# MJ818_clone_-_all_driver_-_prod.net
KiCad netlist of a schematic drawn in EAGLE
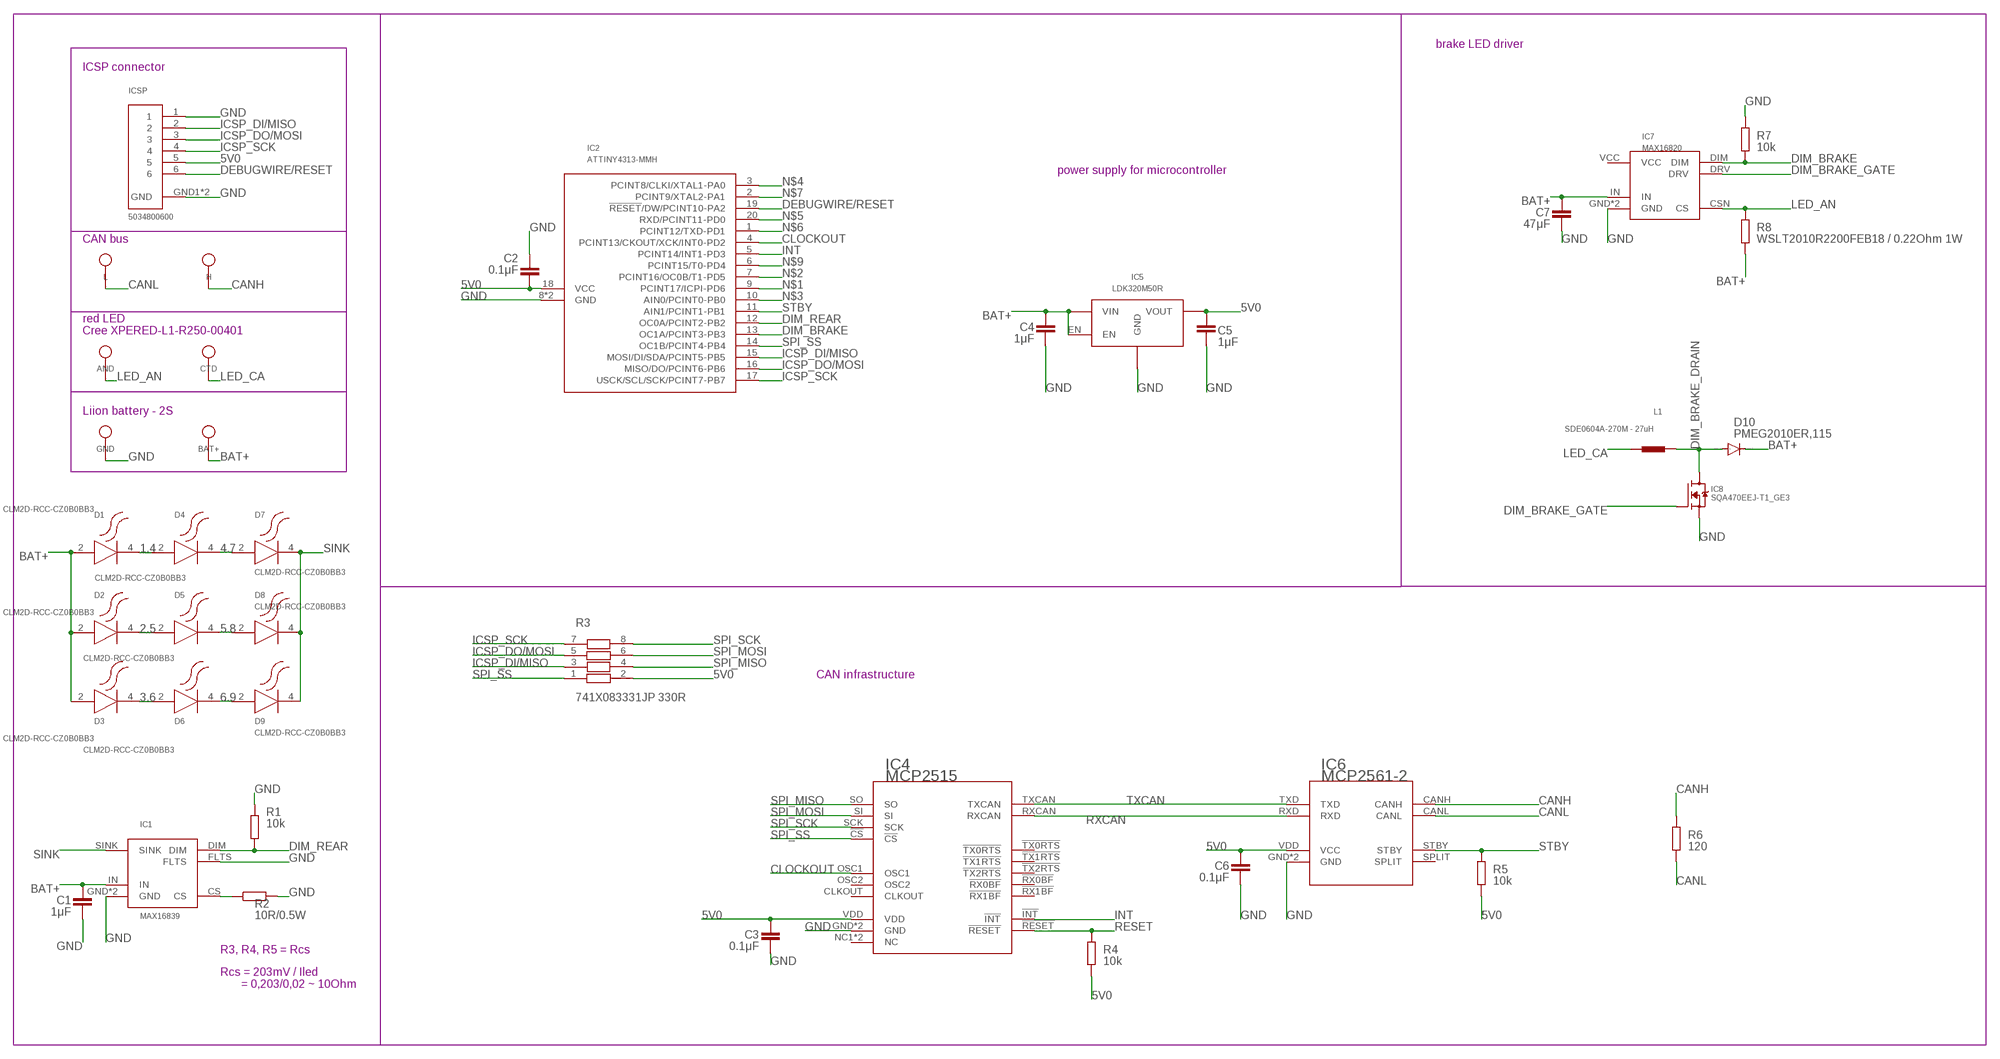
[diagram p0: schematic, sheet 1]

(export (version "E")
  (design (tool "Eeschema 10.0.6"))
  (components
    (comp (ref "AND")
      (value "LED anode")
      (footprint "eagle-import:SMT-1.2MM")
      (libsource (lib "eagle-import") (part "TPSMT-1.2MM"))
    )
    (comp (ref "BAT+")
      (value "bat+")
      (footprint "eagle-import:TH-1.2MM")
      (libsource (lib "eagle-import") (part "TPTH-1.2MM"))
    )
    (comp (ref "C1")
      (value "1μF")
      (footprint "eagle-import:C0402")
      (libsource (lib "eagle-import") (part "C-EUC0402"))
    )
    (comp (ref "C2")
      (value "0.1μF")
      (footprint "eagle-import:C0402")
      (libsource (lib "eagle-import") (part "C-EUC0402"))
    )
    (comp (ref "C3")
      (value "0.1μF")
      (footprint "eagle-import:C0402")
      (libsource (lib "eagle-import") (part "C-EUC0402"))
    )
    (comp (ref "C4")
      (value "1μF")
      (footprint "eagle-import:C0402")
      (libsource (lib "eagle-import") (part "C-EUC0402"))
    )
    (comp (ref "C5")
      (value "1μF")
      (footprint "eagle-import:C0402")
      (libsource (lib "eagle-import") (part "C-EUC0402"))
    )
    (comp (ref "C6")
      (value "0.1μF")
      (footprint "eagle-import:C0402")
      (libsource (lib "eagle-import") (part "C-EUC0402"))
    )
    (comp (ref "C7")
      (value "47μF")
      (footprint "eagle-import:C1206")
      (libsource (lib "eagle-import") (part "C-EUC1206"))
    )
    (comp (ref "CTD")
      (value "LED cathode")
      (footprint "eagle-import:SMT-1.2MM")
      (libsource (lib "eagle-import") (part "TPSMT-1.2MM"))
    )
    (comp (ref "D1")
      (value "CLM2D-RCC-CZ0B0BB3")
      (footprint "eagle-import:SMD")
      (libsource (lib "eagle-import") (part "1374-CLM2D-RCC-ACC-1064252"))
    )
    (comp (ref "D2")
      (value "CLM2D-RCC-CZ0B0BB3")
      (footprint "eagle-import:SMD")
      (libsource (lib "eagle-import") (part "1374-CLM2D-RCC-ACC-1064252"))
    )
    (comp (ref "D3")
      (value "CLM2D-RCC-CZ0B0BB3")
      (footprint "eagle-import:SMD")
      (libsource (lib "eagle-import") (part "1374-CLM2D-RCC-ACC-1064252"))
    )
    (comp (ref "D4")
      (value "CLM2D-RCC-CZ0B0BB3")
      (footprint "eagle-import:SMD")
      (libsource (lib "eagle-import") (part "1374-CLM2D-RCC-ACC-1064252"))
    )
    (comp (ref "D5")
      (value "CLM2D-RCC-CZ0B0BB3")
      (footprint "eagle-import:SMD")
      (libsource (lib "eagle-import") (part "1374-CLM2D-RCC-ACC-1064252"))
    )
    (comp (ref "D6")
      (value "CLM2D-RCC-CZ0B0BB3")
      (footprint "eagle-import:SMD")
      (libsource (lib "eagle-import") (part "1374-CLM2D-RCC-ACC-1064252"))
    )
    (comp (ref "D7")
      (value "CLM2D-RCC-CZ0B0BB3")
      (footprint "eagle-import:SMD")
      (libsource (lib "eagle-import") (part "1374-CLM2D-RCC-ACC-1064252"))
    )
    (comp (ref "D8")
      (value "CLM2D-RCC-CZ0B0BB3")
      (footprint "eagle-import:SMD")
      (libsource (lib "eagle-import") (part "1374-CLM2D-RCC-ACC-1064252"))
    )
    (comp (ref "D9")
      (value "CLM2D-RCC-CZ0B0BB3")
      (footprint "eagle-import:SMD")
      (libsource (lib "eagle-import") (part "1374-CLM2D-RCC-ACC-1064252"))
    )
    (comp (ref "D10")
      (value "PMEG2010ER,115")
      (footprint "eagle-import:SOD123")
      (libsource (lib "eagle-import") (part "DIODE-SOD123"))
    )
    (comp (ref "GND")
      (value "gnd")
      (footprint "eagle-import:TH-1.2MM")
      (libsource (lib "eagle-import") (part "TPTH-1.2MM"))
    )
    (comp (ref "H")
      (value "LED anode")
      (footprint "eagle-import:TH-1.2MM")
      (libsource (lib "eagle-import") (part "TPTH-1.2MM"))
    )
    (comp (ref "IC1")
      (value "MAX16839")
      (footprint "eagle-import:TDFN-6-EP")
      (libsource (lib "eagle-import") (part "MAX16839"))
    )
    (comp (ref "IC2")
      (value "ATTINY4313-MMH")
      (footprint "eagle-import:VQFN-20")
      (fields (field (name "SPICEPREFIX") "X"))
      (libsource (lib "eagle-import") (part "ATTINY4313VQFN-20"))
    )
    (comp (ref "IC4")
      (value "MCP2515")
      (footprint "eagle-import:QFN20")
      (libsource (lib "eagle-import") (part "MCP2515-I-ML"))
    )
    (comp (ref "IC5")
      (value "LDK320M50R")
      (footprint "eagle-import:SOT-23-5L")
      (libsource (lib "eagle-import") (part "LDK320SOT-23-5L"))
    )
    (comp (ref "IC6")
      (value "MCP2561-2")
      (footprint "eagle-import:DFN10")
      (libsource (lib "eagle-import") (part "MCP2561-2"))
    )
    (comp (ref "IC7")
      (value "MAX16820")
      (footprint "eagle-import:TDFN-6-EP")
      (libsource (lib "eagle-import") (part "MAX16820"))
    )
    (comp (ref "IC8")
      (value "SQA470EEJ-T1_GE3")
      (footprint "eagle-import:SC-70-6")
      (libsource (lib "eagle-import") (part "SIA456DJ"))
    )
    (comp (ref "ICSP")
      (value "5034800600")
      (footprint "eagle-import:SMT")
      (libsource (lib "eagle-import") (part "5034800600"))
    )
    (comp (ref "L")
      (value "LED anode")
      (footprint "eagle-import:TH-1.2MM")
      (libsource (lib "eagle-import") (part "TPTH-1.2MM"))
    )
    (comp (ref "L1")
      (value "SDE0604A-270M - 27uH")
      (footprint "eagle-import:SMT")
      (libsource (lib "eagle-import") (part "DE0604A-778075"))
    )
    (comp (ref "R1")
      (value "10k")
      (footprint "eagle-import:R0402")
      (libsource (lib "eagle-import") (part "R-EU_R0402"))
    )
    (comp (ref "R2")
      (value "10R/0.5W")
      (footprint "eagle-import:R0603")
      (libsource (lib "eagle-import") (part "R-EU_R0603"))
    )
    (comp (ref "R3")
      (value "741X083331JP 330R")
      (footprint "eagle-import:0402")
      (libsource (lib "eagle-import") (part "741X083331JP"))
    )
    (comp (ref "R4")
      (value "10k")
      (footprint "eagle-import:R0402")
      (libsource (lib "eagle-import") (part "R-EU_R0402"))
    )
    (comp (ref "R5")
      (value "10k")
      (footprint "eagle-import:R0402")
      (libsource (lib "eagle-import") (part "R-EU_R0402"))
    )
    (comp (ref "R6")
      (value "120")
      (footprint "eagle-import:R0805")
      (libsource (lib "eagle-import") (part "R-EU_R0805"))
    )
    (comp (ref "R7")
      (value "10k")
      (footprint "eagle-import:R0402")
      (libsource (lib "eagle-import") (part "R-EU_R0402"))
    )
    (comp (ref "R8")
      (value "WSLT2010R2200FEB18 / 0.22Ohm 1W")
      (footprint "eagle-import:R2010")
      (libsource (lib "eagle-import") (part "R-EU_R2010"))
    )
  )
  (nets
    (net (code "1") (name "/1.4") (class "Default")
      (node (ref "D1") (pin "4") (pinfunction "C_4") (pintype "bidirectional"))
      (node (ref "D4") (pin "2") (pinfunction "A_2") (pintype "bidirectional"))
    )
    (net (code "2") (name "/2.5") (class "Default")
      (node (ref "D2") (pin "4") (pinfunction "C_4") (pintype "bidirectional"))
      (node (ref "D5") (pin "2") (pinfunction "A_2") (pintype "bidirectional"))
    )
    (net (code "3") (name "/3.6") (class "Default")
      (node (ref "D3") (pin "4") (pinfunction "C_4") (pintype "bidirectional"))
      (node (ref "D6") (pin "2") (pinfunction "A_2") (pintype "bidirectional"))
    )
    (net (code "4") (name "/4.7") (class "Default")
      (node (ref "D4") (pin "4") (pinfunction "C_4") (pintype "bidirectional"))
      (node (ref "D7") (pin "2") (pinfunction "A_2") (pintype "bidirectional"))
    )
    (net (code "5") (name "/5.8") (class "Default")
      (node (ref "D5") (pin "4") (pinfunction "C_4") (pintype "bidirectional"))
      (node (ref "D8") (pin "2") (pinfunction "A_2") (pintype "bidirectional"))
    )
    (net (code "6") (name "/5V0") (class "Default")
      (node (ref "C2") (pin "1") (pinfunction "1_1") (pintype "passive"))
      (node (ref "C3") (pin "1") (pinfunction "1_1") (pintype "passive"))
      (node (ref "C5") (pin "2") (pinfunction "2_2") (pintype "passive"))
      (node (ref "C6") (pin "1") (pinfunction "1_1") (pintype "passive"))
      (node (ref "IC2") (pin "18") (pinfunction "VCC_18") (pintype "bidirectional"))
      (node (ref "IC4") (pin "VDD") (pinfunction "VDD_VDD") (pintype "power_in"))
      (node (ref "IC5") (pin "OUT") (pinfunction "VOUT_OUT") (pintype "bidirectional"))
      (node (ref "IC6") (pin "VDD") (pinfunction "VCC_VDD") (pintype "power_in"))
      (node (ref "ICSP") (pin "5") (pinfunction "5_5") (pintype "bidirectional"))
      (node (ref "R3") (pin "2") (pinfunction "2_2") (pintype "bidirectional"))
      (node (ref "R4") (pin "1") (pinfunction "1_1") (pintype "passive"))
      (node (ref "R5") (pin "1") (pinfunction "1_1") (pintype "passive"))
    )
    (net (code "7") (name "/6.9") (class "Default")
      (node (ref "D6") (pin "4") (pinfunction "C_4") (pintype "bidirectional"))
      (node (ref "D9") (pin "2") (pinfunction "A_2") (pintype "bidirectional"))
    )
    (net (code "8") (name "/BAT+") (class "Default")
      (node (ref "BAT+") (pin "TP$1") (pinfunction "TP$1_TP$1") (pintype "bidirectional"))
      (node (ref "C1") (pin "2") (pinfunction "2_2") (pintype "passive"))
      (node (ref "C4") (pin "1") (pinfunction "1_1") (pintype "passive"))
      (node (ref "C7") (pin "1") (pinfunction "1_1") (pintype "passive"))
      (node (ref "D1") (pin "2") (pinfunction "A_2") (pintype "bidirectional"))
      (node (ref "D10") (pin "C") (pinfunction "C_C") (pintype "passive"))
      (node (ref "D2") (pin "2") (pinfunction "A_2") (pintype "bidirectional"))
      (node (ref "D3") (pin "2") (pinfunction "A_2") (pintype "bidirectional"))
      (node (ref "IC1") (pin "IN") (pinfunction "IN_IN") (pintype "power_in"))
      (node (ref "IC5") (pin "EN") (pinfunction "EN_EN") (pintype "bidirectional"))
      (node (ref "IC5") (pin "IN") (pinfunction "VIN_IN") (pintype "bidirectional"))
      (node (ref "IC7") (pin "IN") (pinfunction "IN_IN") (pintype "power_in"))
      (node (ref "R8") (pin "2") (pinfunction "2_2") (pintype "passive"))
    )
    (net (code "9") (name "/CANH") (class "Default")
      (node (ref "H") (pin "TP$1") (pinfunction "TP$1_TP$1") (pintype "bidirectional"))
      (node (ref "IC6") (pin "CANH") (pinfunction "CANH_CANH") (pintype "bidirectional"))
      (node (ref "R6") (pin "2") (pinfunction "2_2") (pintype "passive"))
    )
    (net (code "10") (name "/CANL") (class "Default")
      (node (ref "IC6") (pin "CANL") (pinfunction "CANL_CANL") (pintype "bidirectional"))
      (node (ref "L") (pin "TP$1") (pinfunction "TP$1_TP$1") (pintype "bidirectional"))
      (node (ref "R6") (pin "1") (pinfunction "1_1") (pintype "passive"))
    )
    (net (code "11") (name "/CLOCKOUT") (class "Default")
      (node (ref "IC2") (pin "4") (pinfunction "PCINT13/CKOUT/XCK/INT0-PD2_4") (pintype "bidirectional"))
      (node (ref "IC4") (pin "OSC1") (pinfunction "OSC1_OSC1") (pintype "bidirectional"))
    )
    (net (code "12") (name "/DEBUGWIRE{slash}RESET") (class "Default")
      (node (ref "IC2") (pin "19") (pinfunction "~{RESET}/DW/PCINT10-PA2_19") (pintype "bidirectional"))
      (node (ref "ICSP") (pin "6") (pinfunction "6_6") (pintype "bidirectional"))
    )
    (net (code "13") (name "/DIM_BRAKE") (class "Default")
      (node (ref "IC2") (pin "13") (pinfunction "OC1A/PCINT3-PB3_13") (pintype "bidirectional"))
      (node (ref "IC7") (pin "DIM") (pinfunction "DIM_DIM") (pintype "bidirectional"))
      (node (ref "R7") (pin "1") (pinfunction "1_1") (pintype "passive"))
    )
    (net (code "14") (name "/DIM_BRAKE_DRAIN") (class "Default")
      (node (ref "D10") (pin "A") (pinfunction "A_A") (pintype "passive"))
      (node (ref "IC8") (pin "1D") (pinfunction "D_1D") (pintype "passive"))
      (node (ref "IC8") (pin "2D") (pinfunction "D_2D") (pintype "passive"))
      (node (ref "IC8") (pin "5D") (pinfunction "D_5D") (pintype "passive"))
      (node (ref "IC8") (pin "6D") (pinfunction "D_6D") (pintype "passive"))
      (node (ref "IC8") (pin "D") (pinfunction "D_D") (pintype "passive"))
      (node (ref "L1") (pin "P$2") (pinfunction "P$2_P$2") (pintype "bidirectional"))
    )
    (net (code "15") (name "/DIM_BRAKE_GATE") (class "Default")
      (node (ref "IC7") (pin "DRV") (pinfunction "DRV_DRV") (pintype "bidirectional"))
      (node (ref "IC8") (pin "3G") (pinfunction "G_3G") (pintype "passive"))
    )
    (net (code "16") (name "/DIM_REAR") (class "Default")
      (node (ref "IC1") (pin "DIM") (pinfunction "DIM_DIM") (pintype "bidirectional"))
      (node (ref "IC2") (pin "12") (pinfunction "OC0A/PCINT2-PB2_12") (pintype "bidirectional"))
      (node (ref "R1") (pin "1") (pinfunction "1_1") (pintype "passive"))
    )
    (net (code "17") (name "/GND") (class "Default")
      (node (ref "C1") (pin "1") (pinfunction "1_1") (pintype "passive"))
      (node (ref "C2") (pin "2") (pinfunction "2_2") (pintype "passive"))
      (node (ref "C3") (pin "2") (pinfunction "2_2") (pintype "passive"))
      (node (ref "C4") (pin "2") (pinfunction "2_2") (pintype "passive"))
      (node (ref "C5") (pin "1") (pinfunction "1_1") (pintype "passive"))
      (node (ref "C6") (pin "2") (pinfunction "2_2") (pintype "passive"))
      (node (ref "C7") (pin "2") (pinfunction "2_2") (pintype "passive"))
      (node (ref "GND") (pin "TP$1") (pinfunction "TP$1_TP$1") (pintype "bidirectional"))
      (node (ref "IC1") (pin "FLTS") (pinfunction "FLTS_FLTS") (pintype "bidirectional"))
      (node (ref "IC1") (pin "GND") (pinfunction "GND_GND") (pintype "power_in"))
      (node (ref "IC1") (pin "GND1") (pinfunction "GND_GND1") (pintype "power_in"))
      (node (ref "IC2") (pin "8") (pinfunction "GND_8") (pintype "bidirectional"))
      (node (ref "IC2") (pin "GND") (pinfunction "GND_GND") (pintype "bidirectional"))
      (node (ref "IC4") (pin "GND") (pinfunction "GND_GND") (pintype "power_in"))
      (node (ref "IC4") (pin "GND6") (pinfunction "GND_GND6") (pintype "power_in"))
      (node (ref "IC5") (pin "GND") (pinfunction "GND_GND") (pintype "bidirectional"))
      (node (ref "IC6") (pin "GND") (pinfunction "GND_GND") (pintype "power_in"))
      (node (ref "IC6") (pin "VSS") (pinfunction "GND_VSS") (pintype "power_in"))
      (node (ref "IC7") (pin "GND") (pinfunction "GND_GND") (pintype "power_in"))
      (node (ref "IC7") (pin "GND1") (pinfunction "GND_GND1") (pintype "power_in"))
      (node (ref "IC8") (pin "4S") (pinfunction "S_4S") (pintype "passive"))
      (node (ref "IC8") (pin "S") (pinfunction "S_S") (pintype "passive"))
      (node (ref "ICSP") (pin "1") (pinfunction "1_1") (pintype "bidirectional"))
      (node (ref "ICSP") (pin "GND1") (pinfunction "GND_GND1") (pintype "bidirectional"))
      (node (ref "ICSP") (pin "GND2") (pinfunction "GND_GND2") (pintype "bidirectional"))
      (node (ref "R1") (pin "2") (pinfunction "2_2") (pintype "passive"))
      (node (ref "R2") (pin "2") (pinfunction "2_2") (pintype "passive"))
      (node (ref "R7") (pin "2") (pinfunction "2_2") (pintype "passive"))
    )
    (net (code "18") (name "/ICSP_DI{slash}MISO") (class "Default")
      (node (ref "IC2") (pin "15") (pinfunction "MOSI/DI/SDA/PCINT5-PB5_15") (pintype "bidirectional"))
      (node (ref "ICSP") (pin "2") (pinfunction "2_2") (pintype "bidirectional"))
      (node (ref "R3") (pin "3") (pinfunction "3_3") (pintype "bidirectional"))
    )
    (net (code "19") (name "/ICSP_DO{slash}MOSI") (class "Default")
      (node (ref "IC2") (pin "16") (pinfunction "MISO/DO/PCINT6-PB6_16") (pintype "bidirectional"))
      (node (ref "ICSP") (pin "3") (pinfunction "3_3") (pintype "bidirectional"))
      (node (ref "R3") (pin "5") (pinfunction "5_5") (pintype "bidirectional"))
    )
    (net (code "20") (name "/ICSP_SCK") (class "Default")
      (node (ref "IC2") (pin "17") (pinfunction "USCK/SCL/SCK/PCINT7-PB7_17") (pintype "bidirectional"))
      (node (ref "ICSP") (pin "4") (pinfunction "4_4") (pintype "bidirectional"))
      (node (ref "R3") (pin "7") (pinfunction "7_7") (pintype "bidirectional"))
    )
    (net (code "21") (name "/INT") (class "Default")
      (node (ref "IC2") (pin "5") (pinfunction "PCINT14/INT1-PD3_5") (pintype "bidirectional"))
      (node (ref "IC4") (pin "!INT!") (pinfunction "~{INT}_!INT!") (pintype "bidirectional"))
    )
    (net (code "22") (name "/LED_AN") (class "Default")
      (node (ref "AND") (pin "P$1") (pinfunction "TP$1_P$1") (pintype "bidirectional"))
      (node (ref "IC7") (pin "CSN") (pinfunction "CS_CSN") (pintype "bidirectional"))
      (node (ref "R8") (pin "1") (pinfunction "1_1") (pintype "passive"))
    )
    (net (code "23") (name "/LED_CA") (class "Default")
      (node (ref "CTD") (pin "P$1") (pinfunction "TP$1_P$1") (pintype "bidirectional"))
      (node (ref "L1") (pin "P$1") (pinfunction "P$1_P$1") (pintype "bidirectional"))
    )
    (net (code "24") (name "/N$1") (class "Default")
      (node (ref "IC2") (pin "9") (pinfunction "PCINT17/ICPI-PD6_9") (pintype "bidirectional"))
    )
    (net (code "25") (name "/N$2") (class "Default")
      (node (ref "IC2") (pin "7") (pinfunction "PCINT16/OC0B/T1-PD5_7") (pintype "bidirectional"))
    )
    (net (code "26") (name "/N$3") (class "Default")
      (node (ref "IC2") (pin "10") (pinfunction "AIN0/PCINT0-PB0_10") (pintype "bidirectional"))
    )
    (net (code "27") (name "/N$4") (class "Default")
      (node (ref "IC2") (pin "3") (pinfunction "PCINT8/CLKI/XTAL1-PA0_3") (pintype "bidirectional"))
    )
    (net (code "28") (name "/N$5") (class "Default")
      (node (ref "IC2") (pin "20") (pinfunction "RXD/PCINT11-PD0_20") (pintype "bidirectional"))
    )
    (net (code "29") (name "/N$6") (class "Default")
      (node (ref "IC2") (pin "1") (pinfunction "PCINT12/TXD-PD1_1") (pintype "bidirectional"))
    )
    (net (code "30") (name "/N$7") (class "Default")
      (node (ref "IC2") (pin "2") (pinfunction "PCINT9/XTAL2-PA1_2") (pintype "bidirectional"))
    )
    (net (code "31") (name "/N$9") (class "Default")
      (node (ref "IC2") (pin "6") (pinfunction "PCINT15/T0-PD4_6") (pintype "bidirectional"))
    )
    (net (code "32") (name "/RESET") (class "Default")
      (node (ref "IC4") (pin "!RESET!") (pinfunction "~{RESET}_!RESET!") (pintype "bidirectional"))
      (node (ref "R4") (pin "2") (pinfunction "2_2") (pintype "passive"))
    )
    (net (code "33") (name "/RXCAN") (class "Default")
      (node (ref "IC4") (pin "RXCAN") (pinfunction "RXCAN_RXCAN") (pintype "input"))
      (node (ref "IC6") (pin "RXD") (pinfunction "RXD_RXD") (pintype "output"))
    )
    (net (code "34") (name "/SINK") (class "Default")
      (node (ref "D7") (pin "4") (pinfunction "C_4") (pintype "bidirectional"))
      (node (ref "D8") (pin "4") (pinfunction "C_4") (pintype "bidirectional"))
      (node (ref "D9") (pin "4") (pinfunction "C_4") (pintype "bidirectional"))
      (node (ref "IC1") (pin "SINK") (pinfunction "SINK_SINK") (pintype "power_in"))
    )
    (net (code "35") (name "/SPI_MISO") (class "Default")
      (node (ref "IC4") (pin "SO") (pinfunction "SO_SO") (pintype "output"))
      (node (ref "R3") (pin "4") (pinfunction "4_4") (pintype "bidirectional"))
    )
    (net (code "36") (name "/SPI_MOSI") (class "Default")
      (node (ref "IC4") (pin "SI") (pinfunction "SI_SI") (pintype "input"))
      (node (ref "R3") (pin "6") (pinfunction "6_6") (pintype "bidirectional"))
    )
    (net (code "37") (name "/SPI_SCK") (class "Default")
      (node (ref "IC4") (pin "SCK") (pinfunction "SCK_SCK") (pintype "bidirectional"))
      (node (ref "R3") (pin "8") (pinfunction "8_8") (pintype "bidirectional"))
    )
    (net (code "38") (name "/SPI_SS") (class "Default")
      (node (ref "IC2") (pin "14") (pinfunction "OC1B/PCINT4-PB4_14") (pintype "bidirectional"))
      (node (ref "IC4") (pin "!CS!") (pinfunction "~{CS}_!CS!") (pintype "bidirectional"))
      (node (ref "R3") (pin "1") (pinfunction "1_1") (pintype "bidirectional"))
    )
    (net (code "39") (name "/STBY") (class "Default")
      (node (ref "IC2") (pin "11") (pinfunction "AIN1/PCINT1-PB1_11") (pintype "bidirectional"))
      (node (ref "IC6") (pin "STBY") (pinfunction "STBY_STBY") (pintype "bidirectional"))
      (node (ref "R5") (pin "2") (pinfunction "2_2") (pintype "passive"))
    )
    (net (code "40") (name "/TXCAN") (class "Default")
      (node (ref "IC4") (pin "TXCAN") (pinfunction "TXCAN_TXCAN") (pintype "output"))
      (node (ref "IC6") (pin "TXD") (pinfunction "TXD_TXD") (pintype "input"))
    )
    (net (code "41") (name "/VCC") (class "Default")
      (node (ref "IC7") (pin "VCC") (pinfunction "VCC_VCC") (pintype "power_in"))
    )
    (net (code "42") (name "Net-(IC1-PadCS)") (class "Default")
      (node (ref "IC1") (pin "CS") (pinfunction "CS_CS") (pintype "bidirectional"))
      (node (ref "R2") (pin "1") (pinfunction "1_1") (pintype "passive"))
    )
    (net (code "43") (name "unconnected-(IC4-NC-PadNC1)") (class "Default")
      (node (ref "IC4") (pin "NC1") (pinfunction "NC_NC1") (pintype "no_connect"))
    )
    (net (code "44") (name "unconnected-(IC4-NC-PadNC2)") (class "Default")
      (node (ref "IC4") (pin "NC2") (pinfunction "NC_NC2") (pintype "no_connect"))
    )
    (net (code "45") (name "unconnected-(IC4-PadCLKOUT)") (class "Default")
      (node (ref "IC4") (pin "CLKOUT") (pinfunction "CLKOUT_CLKOUT") (pintype "bidirectional"))
    )
    (net (code "46") (name "unconnected-(IC4-PadOSC2)") (class "Default")
      (node (ref "IC4") (pin "OSC2") (pinfunction "OSC2_OSC2") (pintype "bidirectional"))
    )
    (net (code "47") (name "unconnected-(IC4-~{RX0BF}-Pad!RX0BF!)") (class "Default")
      (node (ref "IC4") (pin "!RX0BF!") (pinfunction "~{RX0BF}_!RX0BF!") (pintype "bidirectional"))
    )
    (net (code "48") (name "unconnected-(IC4-~{RX1BF}-Pad!RX1BF!)") (class "Default")
      (node (ref "IC4") (pin "!RX1BF!") (pinfunction "~{RX1BF}_!RX1BF!") (pintype "bidirectional"))
    )
    (net (code "49") (name "unconnected-(IC4-~{TX0RTS}-Pad!TX0RTS!)") (class "Default")
      (node (ref "IC4") (pin "!TX0RTS!") (pinfunction "~{TX0RTS}_!TX0RTS!") (pintype "bidirectional"))
    )
    (net (code "50") (name "unconnected-(IC4-~{TX1RTS}-Pad!TX1RTS!)") (class "Default")
      (node (ref "IC4") (pin "!TX1RTS!") (pinfunction "~{TX1RTS}_!TX1RTS!") (pintype "bidirectional"))
    )
    (net (code "51") (name "unconnected-(IC4-~{TX2RTS}-Pad!TX2RTS!)") (class "Default")
      (node (ref "IC4") (pin "!TX2RTS!") (pinfunction "~{TX2RTS}_!TX2RTS!") (pintype "bidirectional"))
    )
    (net (code "52") (name "unconnected-(IC6-PadSPLIT)") (class "Default")
      (node (ref "IC6") (pin "SPLIT") (pinfunction "SPLIT_SPLIT") (pintype "bidirectional"))
    )
  )
)
